# RGB_LED.net
KiCad netlist of a schematic drawn in Altium Designer
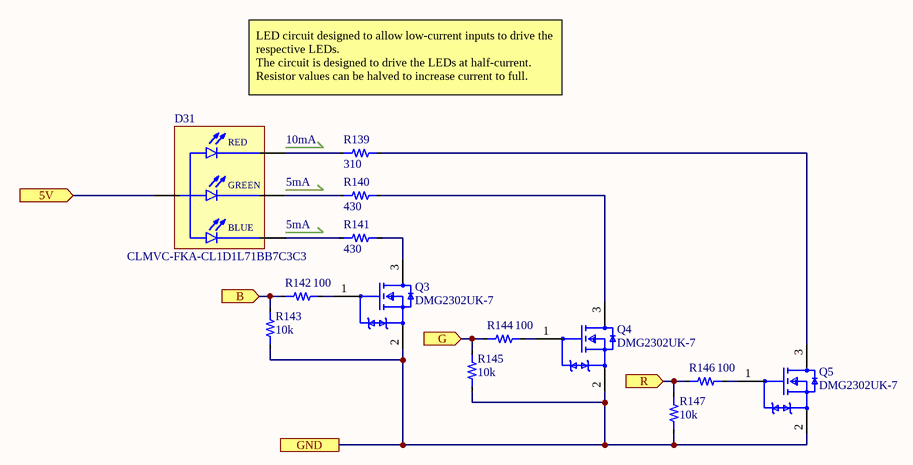
[diagram p0: RGB_LED.SchDoc]

(export (version "E")
  (design (tool "Eeschema 10.0.6"))
  (components
    (comp (ref "D31")
      (value "CLMVC-FKA-CL1D1L71BB7C3C3")
      (footprint "4PLCC CreeLED")
      (fields (field (name "MF") "Cree Inc."))
      (libsource (lib "Diodes") (part "CLMVC-FKA-CL1D1L71BB7C3C3"))
    )
    (comp (ref "Q3")
      (value "DMG2302UK-7")
      (footprint "SOT23-3")
      (description "MOSFET N-CH 20V 2.8A SOT23")
      (fields
        (field (name "OCTOPART") "https://octopart.com/dmg2302uk-7-diodes+inc.-73850182")
        (field (name "MANUFACTURER") "Diodes Inc.")
      )
      (libsource (lib "FETs") (part "DMG2302UK-7"))
    )
    (comp (ref "Q4")
      (value "DMG2302UK-7")
      (footprint "SOT23-3")
      (description "MOSFET N-CH 20V 2.8A SOT23")
      (fields
        (field (name "OCTOPART") "https://octopart.com/dmg2302uk-7-diodes+inc.-73850182")
        (field (name "MANUFACTURER") "Diodes Inc.")
      )
      (libsource (lib "FETs") (part "DMG2302UK-7"))
    )
    (comp (ref "Q5")
      (value "DMG2302UK-7")
      (footprint "SOT23-3")
      (description "MOSFET N-CH 20V 2.8A SOT23")
      (fields
        (field (name "OCTOPART") "https://octopart.com/dmg2302uk-7-diodes+inc.-73850182")
        (field (name "MANUFACTURER") "Diodes Inc.")
      )
      (libsource (lib "FETs") (part "DMG2302UK-7"))
    )
    (comp (ref "R139")
      (value "310")
      (footprint "0603_RES")
      (fields (field (name "Comment") "Resistor"))
      (libsource (lib "Resistors") (part "Resistor"))
    )
    (comp (ref "R140")
      (value "430")
      (footprint "0603_RES")
      (fields (field (name "Comment") "Resistor"))
      (libsource (lib "Resistors") (part "Resistor"))
    )
    (comp (ref "R141")
      (value "430")
      (footprint "0603_RES")
      (fields (field (name "Comment") "Resistor"))
      (libsource (lib "Resistors") (part "Resistor"))
    )
    (comp (ref "R142")
      (value "100")
      (footprint "0603_RES")
      (fields (field (name "Comment") "Resistor"))
      (libsource (lib "Resistors") (part "Resistor"))
    )
    (comp (ref "R143")
      (value "10k")
      (footprint "0603_RES")
      (fields (field (name "Comment") "Resistor"))
      (libsource (lib "Resistors") (part "Resistor"))
    )
    (comp (ref "R144")
      (value "100")
      (footprint "0603_RES")
      (fields (field (name "Comment") "Resistor"))
      (libsource (lib "Resistors") (part "Resistor"))
    )
    (comp (ref "R145")
      (value "10k")
      (footprint "0603_RES")
      (fields (field (name "Comment") "Resistor"))
      (libsource (lib "Resistors") (part "Resistor"))
    )
    (comp (ref "R146")
      (value "100")
      (footprint "0603_RES")
      (fields (field (name "Comment") "Resistor"))
      (libsource (lib "Resistors") (part "Resistor"))
    )
    (comp (ref "R147")
      (value "10k")
      (footprint "0603_RES")
      (fields (field (name "Comment") "Resistor"))
      (libsource (lib "Resistors") (part "Resistor"))
    )
  )
  (nets
    (net (code "1") (name "/5V") (class "Default")
      (node (ref "D31") (pin "1") (pinfunction "A_1") (pintype "passive"))
    )
    (net (code "2") (name "/B") (class "Default")
      (node (ref "R142") (pin "1") (pinfunction "1_1") (pintype "passive"))
      (node (ref "R143") (pin "2") (pinfunction "2_2") (pintype "passive"))
    )
    (net (code "3") (name "/G") (class "Default")
      (node (ref "R144") (pin "1") (pinfunction "1_1") (pintype "passive"))
      (node (ref "R145") (pin "2") (pinfunction "2_2") (pintype "passive"))
    )
    (net (code "4") (name "/GND") (class "Default")
      (node (ref "Q3") (pin "2") (pinfunction "S_2") (pintype "passive"))
      (node (ref "Q4") (pin "2") (pinfunction "S_2") (pintype "passive"))
      (node (ref "Q5") (pin "2") (pinfunction "S_2") (pintype "passive"))
      (node (ref "R143") (pin "1") (pinfunction "1_1") (pintype "passive"))
      (node (ref "R145") (pin "1") (pinfunction "1_1") (pintype "passive"))
      (node (ref "R147") (pin "1") (pinfunction "1_1") (pintype "passive"))
    )
    (net (code "5") (name "/R") (class "Default")
      (node (ref "R146") (pin "1") (pinfunction "1_1") (pintype "passive"))
      (node (ref "R147") (pin "2") (pinfunction "2_2") (pintype "passive"))
    )
    (net (code "6") (name "Net-(D31-B_C)") (class "Default")
      (node (ref "D31") (pin "2") (pinfunction "B_C_2") (pintype "passive"))
      (node (ref "R141") (pin "1") (pinfunction "1_1") (pintype "passive"))
    )
    (net (code "7") (name "Net-(D31-G_C)") (class "Default")
      (node (ref "D31") (pin "3") (pinfunction "G_C_3") (pintype "passive"))
      (node (ref "R140") (pin "1") (pinfunction "1_1") (pintype "passive"))
    )
    (net (code "8") (name "Net-(D31-R_C)") (class "Default")
      (node (ref "D31") (pin "4") (pinfunction "R_C_4") (pintype "passive"))
      (node (ref "R139") (pin "1") (pinfunction "1_1") (pintype "passive"))
    )
    (net (code "9") (name "Net-(Q3-D)") (class "Default")
      (node (ref "Q3") (pin "3") (pinfunction "D_3") (pintype "passive"))
      (node (ref "R141") (pin "2") (pinfunction "2_2") (pintype "passive"))
    )
    (net (code "10") (name "Net-(Q3-G)") (class "Default")
      (node (ref "Q3") (pin "1") (pinfunction "G_1") (pintype "passive"))
      (node (ref "R142") (pin "2") (pinfunction "2_2") (pintype "passive"))
    )
    (net (code "11") (name "Net-(Q4-D)") (class "Default")
      (node (ref "Q4") (pin "3") (pinfunction "D_3") (pintype "passive"))
      (node (ref "R140") (pin "2") (pinfunction "2_2") (pintype "passive"))
    )
    (net (code "12") (name "Net-(Q4-G)") (class "Default")
      (node (ref "Q4") (pin "1") (pinfunction "G_1") (pintype "passive"))
      (node (ref "R144") (pin "2") (pinfunction "2_2") (pintype "passive"))
    )
    (net (code "13") (name "Net-(Q5-D)") (class "Default")
      (node (ref "Q5") (pin "3") (pinfunction "D_3") (pintype "passive"))
      (node (ref "R139") (pin "2") (pinfunction "2_2") (pintype "passive"))
    )
    (net (code "14") (name "Net-(Q5-G)") (class "Default")
      (node (ref "Q5") (pin "1") (pinfunction "G_1") (pintype "passive"))
      (node (ref "R146") (pin "2") (pinfunction "2_2") (pintype "passive"))
    )
  )
)
